# power.net
KiCad netlist of a schematic drawn in Altium Designer
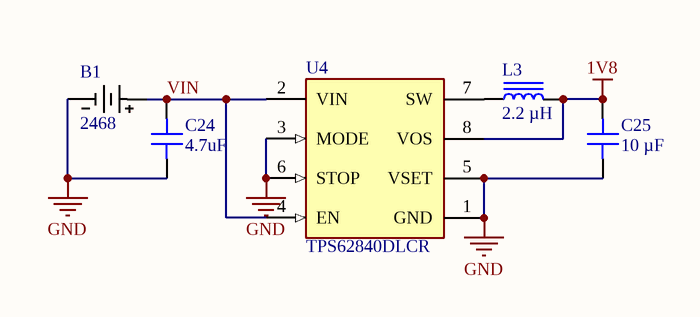
[diagram p0: power.SchDoc]

(export (version "E")
  (design (tool "Eeschema 10.0.6"))
  (components
    (comp (ref "B1")
      (value "2468")
      (footprint "2468_KEY")
      (description "No Description Available")
      (fields (field (name "COPYRIGHT") "Copyright (C) 2022 Ultra Librarian. All rights reserved."))
      (libsource (lib "2468") (part "2468"))
    )
    (comp (ref "C24")
      (value "4.7uF")
      (footprint "CAP 0603_1608")
      (description "CAP CER 10UF 6.3V X5R 0603")
      (fields
        (field (name "PART NUMBER") "GRM188R60J106ME47D")
        (field (name "MANUFACTURER") "Murata Electronics")
      )
      (libsource (lib "Celestial Altium Library - altium_library") (part "Capacitor"))
    )
    (comp (ref "C25")
      (value "10 µF")
      (footprint "CAP 0603_1608")
      (description "CAP CER 10UF 6.3V X5R 0603")
      (fields
        (field (name "PART NUMBER") "GRM188R60J106ME47D")
        (field (name "MANUFACTURER") "Murata Electronics")
      )
      (libsource (lib "Celestial Altium Library - altium_library") (part "Capacitor"))
    )
    (comp (ref "L3")
      (value "2.2 µH")
      (footprint "TDK VLS201612CX")
      (description "FIXED IND 6.8UH 930MA 368MOHM SM")
      (fields
        (field (name "PART NUMBER") "VLS201612CX-6R8M-1")
        (field (name "MANUFACTURER") "TDK Corporation")
      )
      (libsource (lib "Celestial Altium Library - altium_library") (part "Inductor"))
    )
    (comp (ref "U4")
      (value "TPS62840DLCR")
      (footprint "FP-DLC0008B-MFG")
      (description "ULTRA LOW IQ BUCK CONVERTER")
      (fields
        (field (name "OCTOPART") "https://octopart.com/tps62840dlcr-texas+instruments-103121111")
        (field (name "MANUFACTURER") "Texas Instruments")
      )
      (libsource (lib "Altium Content Vault") (part "09bc3a9b1d58a1376198d6b923e8c7c"))
    )
  )
  (nets
    (net (code "1") (name "/VIN") (class "Default")
      (node (ref "B1") (pin "1") (pinfunction "1_1") (pintype "passive"))
      (node (ref "C24") (pin "2") (pinfunction "2_2") (pintype "passive"))
      (node (ref "U4") (pin "2") (pinfunction "VIN_2") (pintype "power_in"))
      (node (ref "U4") (pin "4") (pinfunction "EN_4") (pintype "input"))
    )
    (net (code "2") (name "1V8") (class "Default")
      (node (ref "C25") (pin "2") (pinfunction "2_2") (pintype "passive"))
      (node (ref "L3") (pin "2") (pinfunction "2_2") (pintype "passive"))
      (node (ref "U4") (pin "8") (pinfunction "VOS_8") (pintype "passive"))
    )
    (net (code "3") (name "GND") (class "Default")
      (node (ref "B1") (pin "2") (pinfunction "2_2") (pintype "passive"))
      (node (ref "C24") (pin "1") (pinfunction "1_1") (pintype "passive"))
      (node (ref "C25") (pin "1") (pinfunction "1_1") (pintype "passive"))
      (node (ref "U4") (pin "1") (pinfunction "GND_1") (pintype "power_in"))
      (node (ref "U4") (pin "3") (pinfunction "MODE_3") (pintype "input"))
      (node (ref "U4") (pin "5") (pinfunction "VSET_5") (pintype "passive"))
      (node (ref "U4") (pin "6") (pinfunction "STOP_6") (pintype "input"))
    )
    (net (code "4") (name "Net-(U4-SW)") (class "Default")
      (node (ref "L3") (pin "1") (pinfunction "1_1") (pintype "passive"))
      (node (ref "U4") (pin "7") (pinfunction "SW_7") (pintype "passive"))
    )
  )
)
